# task1_sh1.net
KiCad netlist of a schematic drawn in Altium Designer
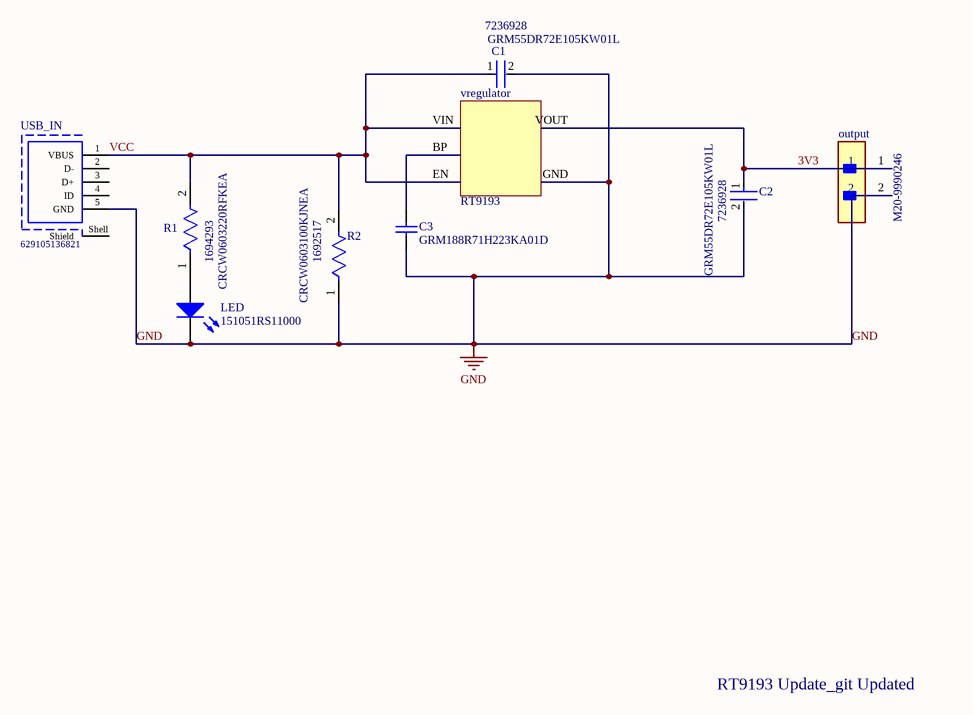
[diagram p0: task1_sh1.SchDoc]

(export (version "E")
  (design (tool "Eeschema 10.0.6"))
  (components
    (comp (ref "C1")
      (value "GRM55DR72E105KW01L")
      (footprint "FP-GRM55D-0_4-IPC_A")
      (description "Chip Multilayer Ceramic Capacitors for General Purpose, 2220, 1.0uF, X7R, 15%, 10%, 250V")
      (fields
        (field (name "VOLTAGE") "250V")
        (field (name "TOLERANCE") "10%")
        (field (name "SUPPLIER PART NUMBER 1") "7236928")
      )
      (libsource (lib "Altium Content Vault") (part "b4654b650e69147ec39a6b967a45e02"))
    )
    (comp (ref "C2")
      (value "GRM55DR72E105KW01L")
      (footprint "FP-GRM55D-0_4-IPC_A")
      (description "Chip Multilayer Ceramic Capacitors for General Purpose, 2220, 1.0uF, X7R, 15%, 10%, 250V")
      (fields
        (field (name "VOLTAGE") "250V")
        (field (name "TOLERANCE") "10%")
        (field (name "SUPPLIER PART NUMBER 1") "7236928")
      )
      (libsource (lib "Altium Content Vault") (part "b4654b650e69147ec39a6b967a45e02"))
    )
    (comp (ref "C3")
      (value "GRM188R71H223KA01D")
      (footprint "CAPC1608X90X35ML10T15")
      (fields (field (name "MANUFACTURER") "Murata"))
      (libsource (lib "Altium Content Vault") (part "CAP"))
    )
    (comp (ref "LED")
      (value "151051RS11000")
      (footprint "Type 5mm")
      (description "THT LED round mono-color color lens, WL-TMRW, Red")
      (fields (field (name "MANUFACTURER") "Wuerth Elektronik"))
      (libsource (lib "Altium Content Vault") (part "WE-LED_K1A2-2"))
    )
    (comp (ref "output")
      (value "M20-9990246")
      (footprint "FP-M20-9990246-MFG")
      (description "CONN HEADER VERT 2POS 2.54MM")
      (fields
        (field (name "OCTOPART") "https://octopart.com/m20-9990246-harwin-2590635")
        (field (name "MANUFACTURER") "Harwin")
      )
      (libsource (lib "Altium Content Vault") (part "3bc925449376181038e59eaffc5286c"))
    )
    (comp (ref "R1")
      (value "CRCW0603220RFKEA")
      (footprint "FP-CRCW0603-e3-MFG")
      (description "RES Thick Film, 220Ω, 1%, 0.1W, 100ppm/°C, 0603")
      (fields (field (name "TOLERANCE") "1%") (field (name "SUPPLIER PART NUMBER 1") "1694293"))
      (libsource (lib "Altium Content Vault") (part "1029c3af85768c4190bb7ad29bc67b5"))
    )
    (comp (ref "R2")
      (value "CRCW0603100KJNEA")
      (footprint "FP-CRCW0603-e3-IPC_C")
      (description "RES Thick Film, 100kΩ, 5%, 0.1W, 200ppm/°C, 0603")
      (fields (field (name "TOLERANCE") "5%") (field (name "SUPPLIER PART NUMBER 1") "1692517"))
      (libsource (lib "Altium Content Vault") (part "1029c3af85768c4190bb7ad29bc67b5"))
    )
    (comp (ref "USB_IN")
      (value "629105136821")
      (footprint "629105136821")
      (description "Micro USB 2.0 Type B Receptacle WR-COM, Horizontal, SMT, with Pads and Pegs")
      (fields (field (name "MANUFACTURER") "Wurth Elektronik") (field (name "PUBLISHER") "WurthElektronik"))
      (libsource (lib "Altium Content Vault") (part "WE-USB-5-1SHLD"))
    )
    (comp (ref "vregulator")
      (value "RT9193")
      (footprint "9193new")
      (libsource (lib "rt9193new") (part "Component_1"))
    )
  )
  (nets
    (net (code "1") (name "/3V3") (class "Default")
      (node (ref "C2") (pin "1") (pinfunction "1_1") (pintype "passive"))
      (node (ref "output") (pin "1") (pinfunction "1_1") (pintype "passive"))
      (node (ref "vregulator") (pin "VOUT") (pintype "power_in"))
    )
    (net (code "2") (name "/VCC") (class "Default")
      (node (ref "C1") (pin "1") (pinfunction "1_1") (pintype "passive"))
      (node (ref "R1") (pin "2") (pinfunction "2_2") (pintype "passive"))
      (node (ref "R2") (pin "2") (pinfunction "2_2") (pintype "passive"))
      (node (ref "USB_IN") (pin "1") (pinfunction "VBUS_1") (pintype "passive"))
      (node (ref "vregulator") (pin "EN") (pintype "power_in"))
      (node (ref "vregulator") (pin "VIN") (pintype "power_in"))
    )
    (net (code "3") (name "GND") (class "Default")
      (node (ref "C1") (pin "2") (pinfunction "2_2") (pintype "passive"))
      (node (ref "C2") (pin "2") (pinfunction "2_2") (pintype "passive"))
      (node (ref "C3") (pin "1") (pinfunction "1_1") (pintype "passive"))
      (node (ref "LED") (pin "1") (pinfunction "K_1") (pintype "passive"))
      (node (ref "R2") (pin "1") (pinfunction "1_1") (pintype "passive"))
      (node (ref "USB_IN") (pin "5") (pinfunction "GND_5") (pintype "passive"))
      (node (ref "output") (pin "2") (pinfunction "2_2") (pintype "passive"))
      (node (ref "vregulator") (pin "GND") (pintype "power_in"))
    )
    (net (code "4") (name "Net-(C3-Pad2)") (class "Default")
      (node (ref "C3") (pin "2") (pinfunction "2_2") (pintype "passive"))
      (node (ref "vregulator") (pin "BP") (pintype "power_in"))
    )
    (net (code "5") (name "Net-(LED-A)") (class "Default")
      (node (ref "LED") (pin "2") (pinfunction "A_2") (pintype "passive"))
      (node (ref "R1") (pin "1") (pinfunction "1_1") (pintype "passive"))
    )
    (net (code "6") (name "unconnected-(USB_IN-D+-Pad3)") (class "Default")
      (node (ref "USB_IN") (pin "3") (pinfunction "D+_3") (pintype "passive"))
    )
    (net (code "7") (name "unconnected-(USB_IN-D--Pad2)") (class "Default")
      (node (ref "USB_IN") (pin "2") (pinfunction "D-_2") (pintype "passive"))
    )
    (net (code "8") (name "unconnected-(USB_IN-ID-Pad4)") (class "Default")
      (node (ref "USB_IN") (pin "4") (pinfunction "ID_4") (pintype "passive"))
    )
    (net (code "9") (name "unconnected-(USB_IN-Shield-PadShell)") (class "Default")
      (node (ref "USB_IN") (pin "Shell") (pinfunction "Shield_Shell") (pintype "passive"))
    )
  )
)
